# 2AD66-SMA.net
KiCad netlist of a schematic drawn in EAGLE
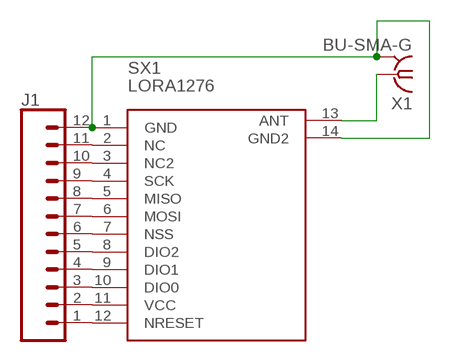
[diagram p0: schematic, sheet 1]

(export (version "E")
  (design (tool "Eeschema 10.0.6"))
  (components
    (comp (ref "J1")
      (value "CONN_12")
      (footprint "eagle-import:1X12")
      (libsource (lib "eagle-import") (part "CONN_12"))
    )
    (comp (ref "SX1")
      (value "LORA1276")
      (footprint "eagle-import:PCBV2")
      (libsource (lib "eagle-import") (part "LORA1276"))
    )
    (comp (ref "X1")
      (value "BU-SMA-G")
      (footprint "eagle-import:BU-SMA-G")
      (libsource (lib "eagle-import") (part "BU-SMA-G"))
    )
  )
  (nets
    (net (code "1") (name "Net-(SX1-ANT)") (class "Default")
      (node (ref "SX1") (pin "13") (pinfunction "ANT_13") (pintype "bidirectional"))
      (node (ref "X1") (pin "1") (pinfunction "1_1") (pintype "passive"))
    )
    (net (code "2") (name "Net-(SX1-DIO0)") (class "Default")
      (node (ref "J1") (pin "3") (pinfunction "3_3") (pintype "passive"))
      (node (ref "SX1") (pin "10") (pinfunction "DIO0_10") (pintype "bidirectional"))
    )
    (net (code "3") (name "Net-(SX1-DIO1)") (class "Default")
      (node (ref "J1") (pin "4") (pinfunction "4_4") (pintype "passive"))
      (node (ref "SX1") (pin "9") (pinfunction "DIO1_9") (pintype "bidirectional"))
    )
    (net (code "4") (name "Net-(SX1-DIO2)") (class "Default")
      (node (ref "J1") (pin "5") (pinfunction "5_5") (pintype "passive"))
      (node (ref "SX1") (pin "8") (pinfunction "DIO2_8") (pintype "bidirectional"))
    )
    (net (code "5") (name "Net-(SX1-GND)") (class "Default")
      (node (ref "J1") (pin "12") (pinfunction "12_12") (pintype "passive"))
      (node (ref "SX1") (pin "1") (pinfunction "GND_1") (pintype "bidirectional"))
      (node (ref "SX1") (pin "14") (pinfunction "GND2_14") (pintype "bidirectional"))
      (node (ref "X1") (pin "2") (pinfunction "2_2") (pintype "passive"))
      (node (ref "X1") (pin "3") (pinfunction "2_3") (pintype "passive"))
      (node (ref "X1") (pin "4") (pinfunction "2_4") (pintype "passive"))
      (node (ref "X1") (pin "5") (pinfunction "2_5") (pintype "passive"))
    )
    (net (code "6") (name "Net-(SX1-MISO)") (class "Default")
      (node (ref "J1") (pin "8") (pinfunction "8_8") (pintype "passive"))
      (node (ref "SX1") (pin "5") (pinfunction "MISO_5") (pintype "bidirectional"))
    )
    (net (code "7") (name "Net-(SX1-MOSI)") (class "Default")
      (node (ref "J1") (pin "7") (pinfunction "7_7") (pintype "passive"))
      (node (ref "SX1") (pin "6") (pinfunction "MOSI_6") (pintype "bidirectional"))
    )
    (net (code "8") (name "Net-(SX1-NC)") (class "Default")
      (node (ref "J1") (pin "11") (pinfunction "11_11") (pintype "passive"))
      (node (ref "SX1") (pin "2") (pinfunction "NC_2") (pintype "bidirectional"))
    )
    (net (code "9") (name "Net-(SX1-NC2)") (class "Default")
      (node (ref "J1") (pin "10") (pinfunction "10_10") (pintype "passive"))
      (node (ref "SX1") (pin "3") (pinfunction "NC2_3") (pintype "bidirectional"))
    )
    (net (code "10") (name "Net-(SX1-NRESET)") (class "Default")
      (node (ref "J1") (pin "1") (pinfunction "1_1") (pintype "passive"))
      (node (ref "SX1") (pin "12") (pinfunction "NRESET_12") (pintype "bidirectional"))
    )
    (net (code "11") (name "Net-(SX1-NSS)") (class "Default")
      (node (ref "J1") (pin "6") (pinfunction "6_6") (pintype "passive"))
      (node (ref "SX1") (pin "7") (pinfunction "NSS_7") (pintype "bidirectional"))
    )
    (net (code "12") (name "Net-(SX1-SCK)") (class "Default")
      (node (ref "J1") (pin "9") (pinfunction "9_9") (pintype "passive"))
      (node (ref "SX1") (pin "4") (pinfunction "SCK_4") (pintype "bidirectional"))
    )
    (net (code "13") (name "Net-(SX1-VCC)") (class "Default")
      (node (ref "J1") (pin "2") (pinfunction "2_2") (pintype "passive"))
      (node (ref "SX1") (pin "11") (pinfunction "VCC_11") (pintype "bidirectional"))
    )
  )
)
